# Open_door_sensor_scheme.net
KiCad netlist of a schematic drawn in Altium Designer
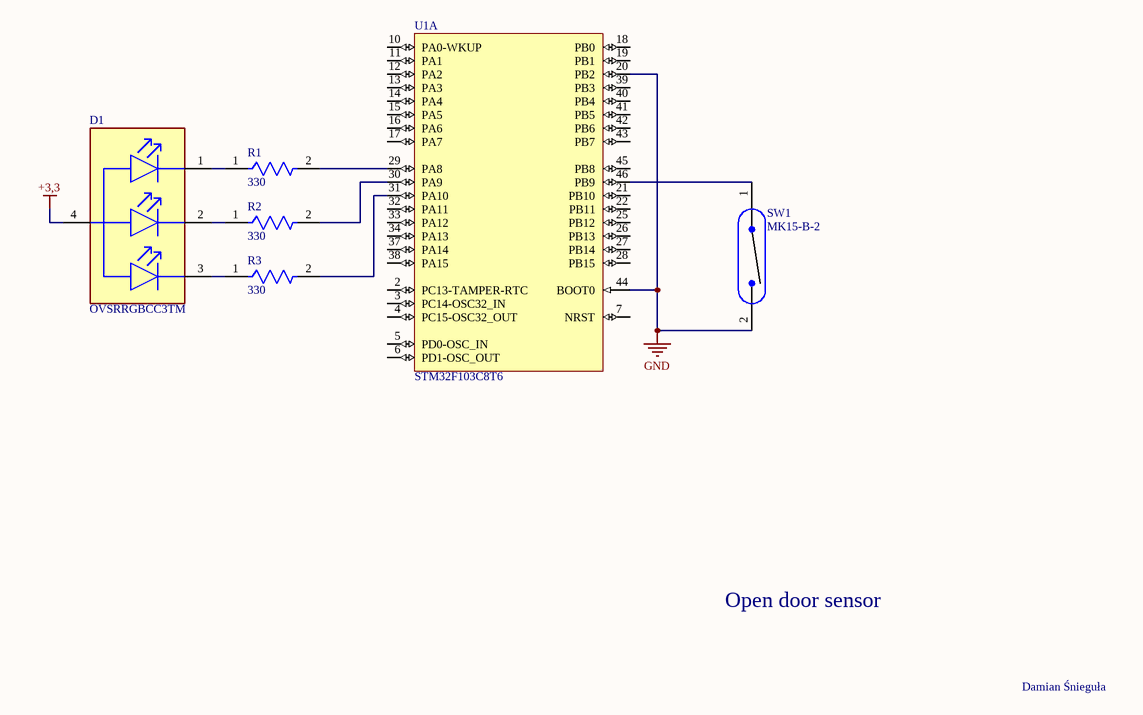
[diagram p0: Open_door_sensor_scheme.SchDoc]

(export (version "E")
  (design (tool "Eeschema 10.0.6"))
  (components
    (comp (ref "D1")
      (value "OVSRRGBCC3TM")
      (footprint "FP-OVSRRGBCC3TM-MFG")
      (description "LED RGB DIFFUSED 1204 SMD")
      (libsource (lib "Altium Content Vault") (part "7312c80c6f37ed131185a1f71a63ae3"))
    )
    (comp (ref "R1")
      (value "330")
      (footprint "FP-CRCW0603-e3-MFG")
      (description "RES Thick Film, 330Ω, 1%, 0.1W, 100ppm/°C, 0603")
      (fields (field (name "TOLERANCE") "1%"))
      (libsource (lib "Altium Content Vault") (part "1029c3af85768c4190bb7ad29bc67b5"))
    )
    (comp (ref "R2")
      (value "330")
      (footprint "FP-CRCW0603-e3-MFG")
      (description "RES Thick Film, 330Ω, 1%, 0.1W, 100ppm/°C, 0603")
      (fields (field (name "TOLERANCE") "1%"))
      (libsource (lib "Altium Content Vault") (part "1029c3af85768c4190bb7ad29bc67b5"))
    )
    (comp (ref "R3")
      (value "330")
      (footprint "FP-CRCW0603-e3-MFG")
      (description "RES Thick Film, 330Ω, 1%, 0.1W, 100ppm/°C, 0603")
      (fields (field (name "TOLERANCE") "1%"))
      (libsource (lib "Altium Content Vault") (part "1029c3af85768c4190bb7ad29bc67b5"))
    )
    (comp (ref "SW1")
      (value "MK15-B-2")
      (footprint "STAN-MK15-B-2_V")
      (description "Reed Sensor, SPST-NO, 10 W, 180 V, -40 to 130 degC, 2-Pin SMD, RoHS, Tape and Reel")
      (fields (field (name "MANUFACTURER") "Standex Meder"))
      (libsource (lib "Altium Content Vault") (part "SW-REED-2"))
    )
    (comp (ref "U1")
      (value "STM32F103C8T6")
      (footprint "STM-LQFP48_L")
      (libsource (lib "Altium Content Vault") (part "MC-ARM-STM32F103X8_B-SQ48"))
    )
  )
  (nets
    (net (code "1") (name "+3,3") (class "Default")
      (node (ref "D1") (pin "4") (pinfunction "COMMON_ANODE_4") (pintype "passive"))
    )
    (net (code "2") (name "GND") (class "Default")
      (node (ref "SW1") (pin "2") (pinfunction "2_2") (pintype "passive"))
      (node (ref "U1") (pin "20") (pinfunction "PB2_20") (pintype "bidirectional"))
      (node (ref "U1") (pin "44") (pinfunction "BOOT0_44") (pintype "input"))
    )
    (net (code "3") (name "Net-(D1-BLUE_C)") (class "Default")
      (node (ref "D1") (pin "3") (pinfunction "BLUE_C_3") (pintype "passive"))
      (node (ref "R3") (pin "1") (pinfunction "1_1") (pintype "passive"))
    )
    (net (code "4") (name "Net-(D1-GREEN_C)") (class "Default")
      (node (ref "D1") (pin "2") (pinfunction "GREEN_C_2") (pintype "passive"))
      (node (ref "R2") (pin "1") (pinfunction "1_1") (pintype "passive"))
    )
    (net (code "5") (name "Net-(D1-RED_C)") (class "Default")
      (node (ref "D1") (pin "1") (pinfunction "RED_C_1") (pintype "passive"))
      (node (ref "R1") (pin "1") (pinfunction "1_1") (pintype "passive"))
    )
    (net (code "6") (name "Net-(U1A-PA8)") (class "Default")
      (node (ref "R1") (pin "2") (pinfunction "2_2") (pintype "passive"))
      (node (ref "U1") (pin "29") (pinfunction "PA8_29") (pintype "bidirectional"))
    )
    (net (code "7") (name "Net-(U1A-PA9)") (class "Default")
      (node (ref "R2") (pin "2") (pinfunction "2_2") (pintype "passive"))
      (node (ref "U1") (pin "30") (pinfunction "PA9_30") (pintype "bidirectional"))
    )
    (net (code "8") (name "Net-(U1A-PA10)") (class "Default")
      (node (ref "R3") (pin "2") (pinfunction "2_2") (pintype "passive"))
      (node (ref "U1") (pin "31") (pinfunction "PA10_31") (pintype "bidirectional"))
    )
    (net (code "9") (name "Net-(U1A-PB9)") (class "Default")
      (node (ref "SW1") (pin "1") (pinfunction "1_1") (pintype "passive"))
      (node (ref "U1") (pin "46") (pinfunction "PB9_46") (pintype "bidirectional"))
    )
    (net (code "10") (name "unconnected-(U1A-NRST-Pad7)") (class "Default")
      (node (ref "U1") (pin "7") (pinfunction "NRST_7") (pintype "bidirectional"))
    )
    (net (code "11") (name "unconnected-(U1A-PA0-WKUP-Pad10)") (class "Default")
      (node (ref "U1") (pin "10") (pinfunction "PA0-WKUP_10") (pintype "bidirectional"))
    )
    (net (code "12") (name "unconnected-(U1A-PA1-Pad11)") (class "Default")
      (node (ref "U1") (pin "11") (pinfunction "PA1_11") (pintype "bidirectional"))
    )
    (net (code "13") (name "unconnected-(U1A-PA2-Pad12)") (class "Default")
      (node (ref "U1") (pin "12") (pinfunction "PA2_12") (pintype "bidirectional"))
    )
    (net (code "14") (name "unconnected-(U1A-PA3-Pad13)") (class "Default")
      (node (ref "U1") (pin "13") (pinfunction "PA3_13") (pintype "bidirectional"))
    )
    (net (code "15") (name "unconnected-(U1A-PA4-Pad14)") (class "Default")
      (node (ref "U1") (pin "14") (pinfunction "PA4_14") (pintype "bidirectional"))
    )
    (net (code "16") (name "unconnected-(U1A-PA5-Pad15)") (class "Default")
      (node (ref "U1") (pin "15") (pinfunction "PA5_15") (pintype "bidirectional"))
    )
    (net (code "17") (name "unconnected-(U1A-PA6-Pad16)") (class "Default")
      (node (ref "U1") (pin "16") (pinfunction "PA6_16") (pintype "bidirectional"))
    )
    (net (code "18") (name "unconnected-(U1A-PA7-Pad17)") (class "Default")
      (node (ref "U1") (pin "17") (pinfunction "PA7_17") (pintype "bidirectional"))
    )
    (net (code "19") (name "unconnected-(U1A-PA11-Pad32)") (class "Default")
      (node (ref "U1") (pin "32") (pinfunction "PA11_32") (pintype "bidirectional"))
    )
    (net (code "20") (name "unconnected-(U1A-PA12-Pad33)") (class "Default")
      (node (ref "U1") (pin "33") (pinfunction "PA12_33") (pintype "bidirectional"))
    )
    (net (code "21") (name "unconnected-(U1A-PA13-Pad34)") (class "Default")
      (node (ref "U1") (pin "34") (pinfunction "PA13_34") (pintype "bidirectional"))
    )
    (net (code "22") (name "unconnected-(U1A-PA14-Pad37)") (class "Default")
      (node (ref "U1") (pin "37") (pinfunction "PA14_37") (pintype "bidirectional"))
    )
    (net (code "23") (name "unconnected-(U1A-PA15-Pad38)") (class "Default")
      (node (ref "U1") (pin "38") (pinfunction "PA15_38") (pintype "bidirectional"))
    )
    (net (code "24") (name "unconnected-(U1A-PB0-Pad18)") (class "Default")
      (node (ref "U1") (pin "18") (pinfunction "PB0_18") (pintype "bidirectional"))
    )
    (net (code "25") (name "unconnected-(U1A-PB1-Pad19)") (class "Default")
      (node (ref "U1") (pin "19") (pinfunction "PB1_19") (pintype "bidirectional"))
    )
    (net (code "26") (name "unconnected-(U1A-PB3-Pad39)") (class "Default")
      (node (ref "U1") (pin "39") (pinfunction "PB3_39") (pintype "bidirectional"))
    )
    (net (code "27") (name "unconnected-(U1A-PB4-Pad40)") (class "Default")
      (node (ref "U1") (pin "40") (pinfunction "PB4_40") (pintype "bidirectional"))
    )
    (net (code "28") (name "unconnected-(U1A-PB5-Pad41)") (class "Default")
      (node (ref "U1") (pin "41") (pinfunction "PB5_41") (pintype "bidirectional"))
    )
    (net (code "29") (name "unconnected-(U1A-PB6-Pad42)") (class "Default")
      (node (ref "U1") (pin "42") (pinfunction "PB6_42") (pintype "bidirectional"))
    )
    (net (code "30") (name "unconnected-(U1A-PB7-Pad43)") (class "Default")
      (node (ref "U1") (pin "43") (pinfunction "PB7_43") (pintype "bidirectional"))
    )
    (net (code "31") (name "unconnected-(U1A-PB8-Pad45)") (class "Default")
      (node (ref "U1") (pin "45") (pinfunction "PB8_45") (pintype "bidirectional"))
    )
    (net (code "32") (name "unconnected-(U1A-PB10-Pad21)") (class "Default")
      (node (ref "U1") (pin "21") (pinfunction "PB10_21") (pintype "bidirectional"))
    )
    (net (code "33") (name "unconnected-(U1A-PB11-Pad22)") (class "Default")
      (node (ref "U1") (pin "22") (pinfunction "PB11_22") (pintype "bidirectional"))
    )
    (net (code "34") (name "unconnected-(U1A-PB12-Pad25)") (class "Default")
      (node (ref "U1") (pin "25") (pinfunction "PB12_25") (pintype "bidirectional"))
    )
    (net (code "35") (name "unconnected-(U1A-PB13-Pad26)") (class "Default")
      (node (ref "U1") (pin "26") (pinfunction "PB13_26") (pintype "bidirectional"))
    )
    (net (code "36") (name "unconnected-(U1A-PB14-Pad27)") (class "Default")
      (node (ref "U1") (pin "27") (pinfunction "PB14_27") (pintype "bidirectional"))
    )
    (net (code "37") (name "unconnected-(U1A-PB15-Pad28)") (class "Default")
      (node (ref "U1") (pin "28") (pinfunction "PB15_28") (pintype "bidirectional"))
    )
    (net (code "38") (name "unconnected-(U1A-PC13-TAMPER-RTC-Pad2)") (class "Default")
      (node (ref "U1") (pin "2") (pinfunction "PC13-TAMPER-RTC_2") (pintype "bidirectional"))
    )
    (net (code "39") (name "unconnected-(U1A-PC14-OSC32_IN-Pad3)") (class "Default")
      (node (ref "U1") (pin "3") (pinfunction "PC14-OSC32_IN_3") (pintype "bidirectional"))
    )
    (net (code "40") (name "unconnected-(U1A-PC15-OSC32_OUT-Pad4)") (class "Default")
      (node (ref "U1") (pin "4") (pinfunction "PC15-OSC32_OUT_4") (pintype "bidirectional"))
    )
    (net (code "41") (name "unconnected-(U1A-PD0-OSC_IN-Pad5)") (class "Default")
      (node (ref "U1") (pin "5") (pinfunction "PD0-OSC_IN_5") (pintype "bidirectional"))
    )
    (net (code "42") (name "unconnected-(U1A-PD1-OSC_OUT-Pad6)") (class "Default")
      (node (ref "U1") (pin "6") (pinfunction "PD1-OSC_OUT_6") (pintype "bidirectional"))
    )
  )
)
